# diffren_amp.net
KiCad netlist of a schematic drawn in EAGLE
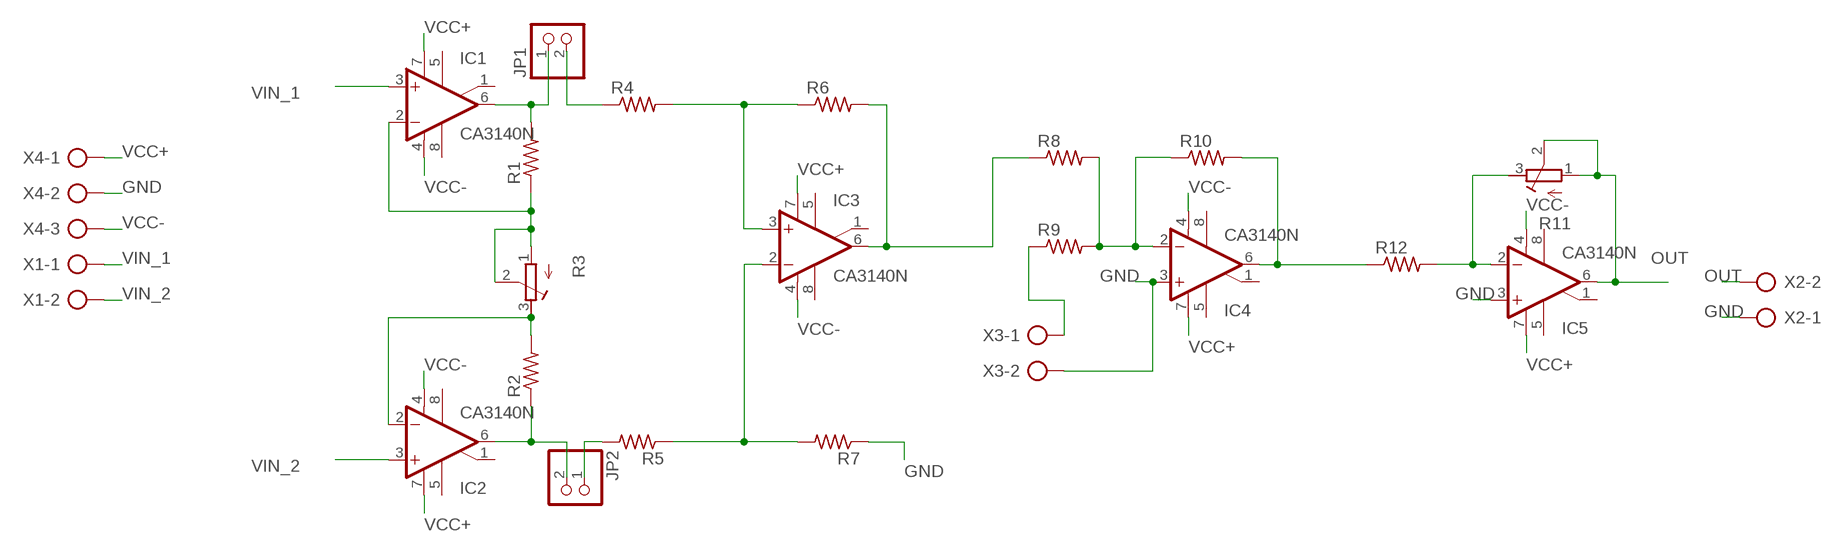
[diagram p0: schematic, sheet 1]

(export (version "E")
  (design (tool "Eeschema 10.0.6"))
  (components
    (comp (ref "IC1")
      (value "CA3140N")
      (footprint "eagle-import:DIL08")
      (libsource (lib "eagle-import") (part "CA3140N"))
    )
    (comp (ref "IC2")
      (value "CA3140N")
      (footprint "eagle-import:DIL08")
      (libsource (lib "eagle-import") (part "CA3140N"))
    )
    (comp (ref "IC3")
      (value "CA3140N")
      (footprint "eagle-import:DIL08")
      (libsource (lib "eagle-import") (part "CA3140N"))
    )
    (comp (ref "IC4")
      (value "CA3140N")
      (footprint "eagle-import:DIL08")
      (libsource (lib "eagle-import") (part "CA3140N"))
    )
    (comp (ref "IC5")
      (value "CA3140N")
      (footprint "eagle-import:DIL08")
      (libsource (lib "eagle-import") (part "CA3140N"))
    )
    (comp (ref "JP1")
      (value "PINHD-1X2")
      (footprint "eagle-import:1X02")
      (libsource (lib "eagle-import") (part "PINHD-1X2"))
    )
    (comp (ref "JP2")
      (value "PINHD-1X2")
      (footprint "eagle-import:1X02")
      (libsource (lib "eagle-import") (part "PINHD-1X2"))
    )
    (comp (ref "R1")
      (value "R-US_0309/12")
      (footprint "eagle-import:0309_12")
      (libsource (lib "eagle-import") (part "R-US_0309/12"))
    )
    (comp (ref "R2")
      (value "R-US_0309/12")
      (footprint "eagle-import:0309_12")
      (libsource (lib "eagle-import") (part "R-US_0309/12"))
    )
    (comp (ref "R3")
      (value "R-TRIMM64W")
      (footprint "eagle-import:RTRIM64W")
      (libsource (lib "eagle-import") (part "R-TRIMM64W"))
    )
    (comp (ref "R4")
      (value "R-US_0309/12")
      (footprint "eagle-import:0309_12")
      (libsource (lib "eagle-import") (part "R-US_0309/12"))
    )
    (comp (ref "R5")
      (value "R-US_0309/12")
      (footprint "eagle-import:0309_12")
      (libsource (lib "eagle-import") (part "R-US_0309/12"))
    )
    (comp (ref "R6")
      (value "R-US_0309/12")
      (footprint "eagle-import:0309_12")
      (libsource (lib "eagle-import") (part "R-US_0309/12"))
    )
    (comp (ref "R7")
      (value "R-US_0309/12")
      (footprint "eagle-import:0309_12")
      (libsource (lib "eagle-import") (part "R-US_0309/12"))
    )
    (comp (ref "R8")
      (value "R-US_0309/12")
      (footprint "eagle-import:0309_12")
      (libsource (lib "eagle-import") (part "R-US_0309/12"))
    )
    (comp (ref "R9")
      (value "R-US_0309/12")
      (footprint "eagle-import:0309_12")
      (libsource (lib "eagle-import") (part "R-US_0309/12"))
    )
    (comp (ref "R10")
      (value "R-US_0309/12")
      (footprint "eagle-import:0309_12")
      (libsource (lib "eagle-import") (part "R-US_0309/12"))
    )
    (comp (ref "R11")
      (value "R-TRIMM64W")
      (footprint "eagle-import:RTRIM64W")
      (libsource (lib "eagle-import") (part "R-TRIMM64W"))
    )
    (comp (ref "R12")
      (value "R-US_0309/12")
      (footprint "eagle-import:0309_12")
      (libsource (lib "eagle-import") (part "R-US_0309/12"))
    )
    (comp (ref "X1")
      (value "AK300/2")
      (footprint "eagle-import:AK300_2")
      (libsource (lib "eagle-import") (part "AK300/2"))
    )
    (comp (ref "X2")
      (value "AK500/2-H")
      (footprint "eagle-import:AK500_2-H")
      (libsource (lib "eagle-import") (part "AK500/2-H"))
    )
    (comp (ref "X3")
      (value "AK500/2-H")
      (footprint "eagle-import:AK500_2-H")
      (libsource (lib "eagle-import") (part "AK500/2-H"))
    )
    (comp (ref "X4")
      (value "AK300/3")
      (footprint "eagle-import:AK300_3")
      (libsource (lib "eagle-import") (part "AK300/3"))
    )
  )
  (nets
    (net (code "1") (name "/GND") (class "Default")
      (node (ref "IC4") (pin "3") (pinfunction "+IN_3") (pintype "input"))
      (node (ref "IC5") (pin "3") (pinfunction "+IN_3") (pintype "input"))
      (node (ref "R7") (pin "1") (pinfunction "1_1") (pintype "passive"))
      (node (ref "X2") (pin "1") (pinfunction "KL_1") (pintype "passive"))
      (node (ref "X3") (pin "2") (pinfunction "KL_2") (pintype "passive"))
      (node (ref "X4") (pin "2") (pinfunction "KL_2") (pintype "passive"))
    )
    (net (code "2") (name "/OUT") (class "Default")
      (node (ref "IC3") (pin "6") (pinfunction "OUT_6") (pintype "output"))
      (node (ref "IC5") (pin "6") (pinfunction "OUT_6") (pintype "output"))
      (node (ref "R11") (pin "1") (pinfunction "A_1") (pintype "passive"))
      (node (ref "R11") (pin "2") (pinfunction "S_2") (pintype "passive"))
      (node (ref "R6") (pin "2") (pinfunction "2_2") (pintype "passive"))
      (node (ref "R8") (pin "1") (pinfunction "1_1") (pintype "passive"))
      (node (ref "X2") (pin "2") (pinfunction "KL_2") (pintype "passive"))
    )
    (net (code "3") (name "/VCC+") (class "Default")
      (node (ref "IC1") (pin "7") (pinfunction "V+_7") (pintype "power_in"))
      (node (ref "IC2") (pin "7") (pinfunction "V+_7") (pintype "power_in"))
      (node (ref "IC3") (pin "7") (pinfunction "V+_7") (pintype "power_in"))
      (node (ref "IC4") (pin "7") (pinfunction "V+_7") (pintype "power_in"))
      (node (ref "IC5") (pin "7") (pinfunction "V+_7") (pintype "power_in"))
      (node (ref "X4") (pin "1") (pinfunction "KL_1") (pintype "passive"))
    )
    (net (code "4") (name "/VCC-") (class "Default")
      (node (ref "IC1") (pin "4") (pinfunction "V-_4") (pintype "power_in"))
      (node (ref "IC2") (pin "4") (pinfunction "V-_4") (pintype "power_in"))
      (node (ref "IC3") (pin "4") (pinfunction "V-_4") (pintype "power_in"))
      (node (ref "IC4") (pin "4") (pinfunction "V-_4") (pintype "power_in"))
      (node (ref "IC5") (pin "4") (pinfunction "V-_4") (pintype "power_in"))
      (node (ref "X4") (pin "3") (pinfunction "KL_3") (pintype "passive"))
    )
    (net (code "5") (name "/VIN_1") (class "Default")
      (node (ref "IC1") (pin "3") (pinfunction "+IN_3") (pintype "input"))
      (node (ref "X1") (pin "1") (pinfunction "KL_1") (pintype "passive"))
    )
    (net (code "6") (name "/VIN_2") (class "Default")
      (node (ref "IC2") (pin "3") (pinfunction "+IN_3") (pintype "input"))
      (node (ref "X1") (pin "2") (pinfunction "KL_2") (pintype "passive"))
    )
    (net (code "7") (name "Net-(IC1--IN)") (class "Default")
      (node (ref "IC1") (pin "2") (pinfunction "-IN_2") (pintype "input"))
      (node (ref "R1") (pin "1") (pinfunction "1_1") (pintype "passive"))
      (node (ref "R3") (pin "1") (pinfunction "A_1") (pintype "passive"))
      (node (ref "R3") (pin "2") (pinfunction "S_2") (pintype "passive"))
    )
    (net (code "8") (name "Net-(IC1-OUT)") (class "Default")
      (node (ref "IC1") (pin "6") (pinfunction "OUT_6") (pintype "output"))
      (node (ref "JP1") (pin "1") (pinfunction "1_1") (pintype "passive"))
      (node (ref "R1") (pin "2") (pinfunction "2_2") (pintype "passive"))
    )
    (net (code "9") (name "Net-(IC2--IN)") (class "Default")
      (node (ref "IC2") (pin "2") (pinfunction "-IN_2") (pintype "input"))
      (node (ref "R2") (pin "2") (pinfunction "2_2") (pintype "passive"))
      (node (ref "R3") (pin "3") (pinfunction "E_3") (pintype "passive"))
    )
    (net (code "10") (name "Net-(IC2-OUT)") (class "Default")
      (node (ref "IC2") (pin "6") (pinfunction "OUT_6") (pintype "output"))
      (node (ref "JP2") (pin "2") (pinfunction "2_2") (pintype "passive"))
      (node (ref "R2") (pin "1") (pinfunction "1_1") (pintype "passive"))
    )
    (net (code "11") (name "Net-(IC3-+IN)") (class "Default")
      (node (ref "IC3") (pin "3") (pinfunction "+IN_3") (pintype "input"))
      (node (ref "R4") (pin "2") (pinfunction "2_2") (pintype "passive"))
      (node (ref "R6") (pin "1") (pinfunction "1_1") (pintype "passive"))
    )
    (net (code "12") (name "Net-(IC3--IN)") (class "Default")
      (node (ref "IC3") (pin "2") (pinfunction "-IN_2") (pintype "input"))
      (node (ref "R5") (pin "1") (pinfunction "1_1") (pintype "passive"))
      (node (ref "R7") (pin "2") (pinfunction "2_2") (pintype "passive"))
    )
    (net (code "13") (name "Net-(IC4--IN)") (class "Default")
      (node (ref "IC4") (pin "2") (pinfunction "-IN_2") (pintype "input"))
      (node (ref "R10") (pin "1") (pinfunction "1_1") (pintype "passive"))
      (node (ref "R8") (pin "2") (pinfunction "2_2") (pintype "passive"))
      (node (ref "R9") (pin "2") (pinfunction "2_2") (pintype "passive"))
    )
    (net (code "14") (name "Net-(IC4-OUT)") (class "Default")
      (node (ref "IC4") (pin "6") (pinfunction "OUT_6") (pintype "output"))
      (node (ref "R10") (pin "2") (pinfunction "2_2") (pintype "passive"))
      (node (ref "R12") (pin "1") (pinfunction "1_1") (pintype "passive"))
    )
    (net (code "15") (name "Net-(IC5--IN)") (class "Default")
      (node (ref "IC5") (pin "2") (pinfunction "-IN_2") (pintype "input"))
      (node (ref "R11") (pin "3") (pinfunction "E_3") (pintype "passive"))
      (node (ref "R12") (pin "2") (pinfunction "2_2") (pintype "passive"))
    )
    (net (code "16") (name "Net-(JP1-Pad2)") (class "Default")
      (node (ref "JP1") (pin "2") (pinfunction "2_2") (pintype "passive"))
      (node (ref "R4") (pin "1") (pinfunction "1_1") (pintype "passive"))
    )
    (net (code "17") (name "Net-(JP2-Pad1)") (class "Default")
      (node (ref "JP2") (pin "1") (pinfunction "1_1") (pintype "passive"))
      (node (ref "R5") (pin "2") (pinfunction "2_2") (pintype "passive"))
    )
    (net (code "18") (name "Net-(X3A-KL)") (class "Default")
      (node (ref "R9") (pin "1") (pinfunction "1_1") (pintype "passive"))
      (node (ref "X3") (pin "1") (pinfunction "KL_1") (pintype "passive"))
    )
    (net (code "19") (name "unconnected-(IC1-CMP-Pad8)") (class "Default")
      (node (ref "IC1") (pin "8") (pinfunction "CMP_8") (pintype "passive"))
    )
    (net (code "20") (name "unconnected-(IC1-ON-Pad5)") (class "Default")
      (node (ref "IC1") (pin "5") (pinfunction "ON_5") (pintype "passive"))
    )
    (net (code "21") (name "unconnected-(IC1-ON{slash}CMP-Pad1)") (class "Default")
      (node (ref "IC1") (pin "1") (pinfunction "ON/CMP_1") (pintype "passive"))
    )
    (net (code "22") (name "unconnected-(IC2-CMP-Pad8)") (class "Default")
      (node (ref "IC2") (pin "8") (pinfunction "CMP_8") (pintype "passive"))
    )
    (net (code "23") (name "unconnected-(IC2-ON-Pad5)") (class "Default")
      (node (ref "IC2") (pin "5") (pinfunction "ON_5") (pintype "passive"))
    )
    (net (code "24") (name "unconnected-(IC2-ON{slash}CMP-Pad1)") (class "Default")
      (node (ref "IC2") (pin "1") (pinfunction "ON/CMP_1") (pintype "passive"))
    )
    (net (code "25") (name "unconnected-(IC3-CMP-Pad8)") (class "Default")
      (node (ref "IC3") (pin "8") (pinfunction "CMP_8") (pintype "passive"))
    )
    (net (code "26") (name "unconnected-(IC3-ON-Pad5)") (class "Default")
      (node (ref "IC3") (pin "5") (pinfunction "ON_5") (pintype "passive"))
    )
    (net (code "27") (name "unconnected-(IC3-ON{slash}CMP-Pad1)") (class "Default")
      (node (ref "IC3") (pin "1") (pinfunction "ON/CMP_1") (pintype "passive"))
    )
    (net (code "28") (name "unconnected-(IC4-CMP-Pad8)") (class "Default")
      (node (ref "IC4") (pin "8") (pinfunction "CMP_8") (pintype "passive"))
    )
    (net (code "29") (name "unconnected-(IC4-ON-Pad5)") (class "Default")
      (node (ref "IC4") (pin "5") (pinfunction "ON_5") (pintype "passive"))
    )
    (net (code "30") (name "unconnected-(IC4-ON{slash}CMP-Pad1)") (class "Default")
      (node (ref "IC4") (pin "1") (pinfunction "ON/CMP_1") (pintype "passive"))
    )
    (net (code "31") (name "unconnected-(IC5-CMP-Pad8)") (class "Default")
      (node (ref "IC5") (pin "8") (pinfunction "CMP_8") (pintype "passive"))
    )
    (net (code "32") (name "unconnected-(IC5-ON-Pad5)") (class "Default")
      (node (ref "IC5") (pin "5") (pinfunction "ON_5") (pintype "passive"))
    )
    (net (code "33") (name "unconnected-(IC5-ON{slash}CMP-Pad1)") (class "Default")
      (node (ref "IC5") (pin "1") (pinfunction "ON/CMP_1") (pintype "passive"))
    )
  )
)
